# BlueBox-Amp_PA.net
KiCad netlist of a schematic drawn in Altium Designer
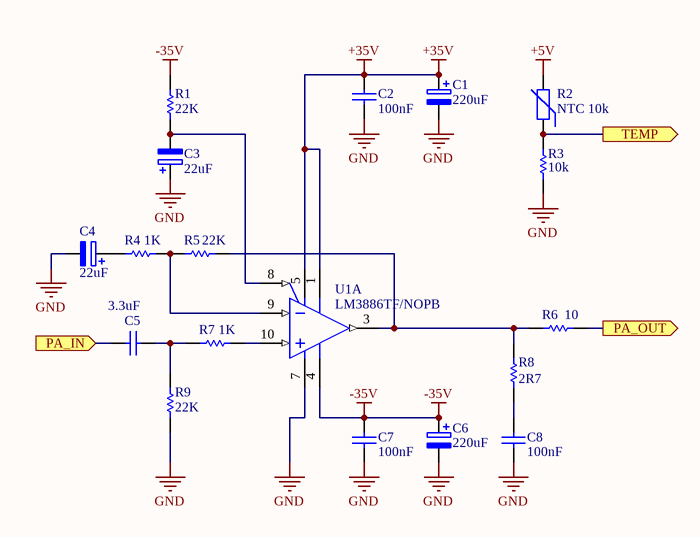
[diagram p0: BlueBox-Amp [PA].SchDoc]

(export (version "E")
  (design (tool "Eeschema 10.0.6"))
  (components
    (comp (ref "C1")
      (value "220uF")
      (footprint "E5-10,5")
      (description "Polarized Capacitor")
      (fields (field (name "Comment") "Capacitor Polarized"))
      (libsource (lib "") (part "Capacitor Polarized_1"))
    )
    (comp (ref "C2")
      (value "100nF")
      (footprint "CAPC0603(1608)100_L")
      (description "CAP 100nF 50V ±5% 0603 (1608 Metric) Thickness 1mm SMD")
      (fields (field (name "TOLERANCE") "±5%") (field (name "Comment") "CAP 100nF 50V 0603(1608)"))
      (libsource (lib "Altium Content Vault") (part "CMP-1035-02591-1"))
    )
    (comp (ref "C3")
      (value "22uF")
      (footprint "EC P2-D5-H11")
      (description "Polarized Capacitor")
      (fields (field (name "Comment") "Capacitor Polarized"))
      (libsource (lib "DEV - RLC") (part "Capacitor Polarized"))
    )
    (comp (ref "C4")
      (value "22uF")
      (footprint "EC P2-D5-H11")
      (description "Polarized Capacitor")
      (fields (field (name "Comment") "Capacitor Polarized"))
      (libsource (lib "") (part "Capacitor Polarized_2"))
    )
    (comp (ref "C5")
      (value "3.3uF")
      (footprint "CAPC1210(3225)280_L")
      (description "CAP 3.3uF 50V ±10% 1210 (3225 Metric) Thickness 2.8mm SMD")
      (fields (field (name "TOLERANCE") "±10%") (field (name "Comment") "CAP 3.3uF 50V 1210(3225)"))
      (libsource (lib "Altium Content Vault") (part "CMP-1038-02126-1"))
    )
    (comp (ref "C6")
      (value "220uF")
      (footprint "E5-10,5")
      (description "Polarized Capacitor")
      (fields (field (name "Comment") "Capacitor Polarized"))
      (libsource (lib "") (part "Capacitor Polarized_1"))
    )
    (comp (ref "C7")
      (value "100nF")
      (footprint "CAPC0603(1608)100_L")
      (description "CAP 100nF 50V ±5% 0603 (1608 Metric) Thickness 1mm SMD")
      (fields (field (name "TOLERANCE") "±5%") (field (name "Comment") "CAP 100nF 50V 0603(1608)"))
      (libsource (lib "Altium Content Vault") (part "CMP-1035-02591-1"))
    )
    (comp (ref "C8")
      (value "100nF")
      (footprint "CAPC0603(1608)100_L")
      (description "CAP 100nF 50V ±5% 0603 (1608 Metric) Thickness 1mm SMD")
      (fields (field (name "TOLERANCE") "±5%") (field (name "Comment") "CAP 100nF 50V 0603(1608)"))
      (libsource (lib "Altium Content Vault") (part "CMP-1035-02591-1"))
    )
    (comp (ref "R1")
      (value "22K")
      (footprint "RESC0603(1608)_L")
      (description "22K 0.1W 1% 0603 (1608 Metric)  SMD")
      (fields (field (name "POWER") "0.1 W") (field (name "TOLERANCE") "1 %"))
      (libsource (lib "Altium Content Vault") (part "CMP-1012-00659-1"))
    )
    (comp (ref "R2")
      (value "NTC 10k")
      (footprint "HDR1X2")
      (description "Thermistors - NTC 10k")
      (fields
        (field (name "MANUFACTURER") "Vishay / BC Components")
        (field (name "MANUFACTURER PART NUMBER") "NTCALUG02A103F")
      )
      (libsource (lib "DEV - Sensor") (part "NTCALUG02A103F"))
    )
    (comp (ref "R3")
      (value "10k")
      (footprint "RESC0603(1608)_M")
      (description "10K 0.1W 1% 0603 (1608 Metric)  SMD")
      (fields (field (name "POWER") "0.1 W") (field (name "TOLERANCE") "1 %"))
      (libsource (lib "Altium Content Vault") (part "CMP-1012-00623-1"))
    )
    (comp (ref "R4")
      (value "1K")
      (footprint "RESC0603(1608)_M")
      (description "1K 0.1W 1% 0603 (1608 Metric)  SMD")
      (fields (field (name "TOLERANCE") "1 %") (field (name "POWER") "0.1 W"))
      (libsource (lib "Altium Content Vault") (part "CMP-1012-00510-1"))
    )
    (comp (ref "R5")
      (value "22K")
      (footprint "RESC0603(1608)_L")
      (description "22K 0.1W 1% 0603 (1608 Metric)  SMD")
      (fields (field (name "POWER") "0.1 W") (field (name "TOLERANCE") "1 %"))
      (libsource (lib "Altium Content Vault") (part "CMP-1012-00659-1"))
    )
    (comp (ref "R6")
      (value "10")
      (footprint "RESC2512(6432)_L")
      (description "10R 1W 5% 2512 (6432 Metric)  SMD")
      (fields (field (name "POWER") "1 W") (field (name "TOLERANCE") "5 %"))
      (libsource (lib "Altium Content Vault") (part "CMP-1018-00026-1"))
    )
    (comp (ref "R7")
      (value "1K")
      (footprint "RESC0603(1608)_M")
      (description "1K 0.1W 1% 0603 (1608 Metric)  SMD")
      (fields (field (name "TOLERANCE") "1 %") (field (name "POWER") "0.1 W"))
      (libsource (lib "Altium Content Vault") (part "CMP-1012-00510-1"))
    )
    (comp (ref "R8")
      (value "2R7")
      (footprint "RESC2512(6432)_L")
      (description "2R7 1W 5% 2512 (6432 Metric)  SMD")
      (fields (field (name "TOLERANCE") "5 %") (field (name "POWER") "1 W"))
      (libsource (lib "Altium Content Vault") (part "CMP-1018-00012-1"))
    )
    (comp (ref "R9")
      (value "22K")
      (footprint "RESC0603(1608)_L")
      (description "22K 0.1W 1% 0603 (1608 Metric)  SMD")
      (fields (field (name "POWER") "0.1 W") (field (name "TOLERANCE") "1 %"))
      (libsource (lib "Altium Content Vault") (part "CMP-1012-00659-1"))
    )
    (comp (ref "U1")
      (value "LM3886TF/NOPB")
      (footprint "TI-NDA11")
      (fields (field (name "MANUFACTURER") "Texas Instruments"))
      (libsource (lib "Altium Content Vault") (part "TI-LM3886undefined"))
    )
  )
  (nets
    (net (code "1") (name "+5V") (class "Default")
      (node (ref "R2") (pin "2") (pinfunction "2_2") (pintype "passive"))
    )
    (net (code "2") (name "+35V") (class "Default")
      (node (ref "C1") (pin "1") (pinfunction "1_1") (pintype "passive"))
      (node (ref "C2") (pin "2") (pinfunction "2_2") (pintype "passive"))
      (node (ref "U1") (pin "1") (pinfunction "V+_1") (pintype "power_in"))
      (node (ref "U1") (pin "5") (pinfunction "V+_5") (pintype "power_in"))
    )
    (net (code "3") (name "-35V") (class "Default")
      (node (ref "C6") (pin "1") (pinfunction "1_1") (pintype "passive"))
      (node (ref "C7") (pin "2") (pinfunction "2_2") (pintype "passive"))
      (node (ref "R1") (pin "1") (pinfunction "1_1") (pintype "passive"))
      (node (ref "U1") (pin "4") (pinfunction "V-_4") (pintype "power_in"))
    )
    (net (code "4") (name "/PA_IN") (class "Default")
      (node (ref "C5") (pin "1") (pinfunction "1_1") (pintype "passive"))
    )
    (net (code "5") (name "/PA_OUT") (class "Default")
      (node (ref "R6") (pin "2") (pinfunction "2_2") (pintype "passive"))
    )
    (net (code "6") (name "/TEMP") (class "Default")
      (node (ref "R2") (pin "1") (pinfunction "1_1") (pintype "passive"))
      (node (ref "R3") (pin "2") (pinfunction "2_2") (pintype "passive"))
    )
    (net (code "7") (name "GND") (class "Default")
      (node (ref "C1") (pin "2") (pinfunction "2_2") (pintype "passive"))
      (node (ref "C2") (pin "1") (pinfunction "1_1") (pintype "passive"))
      (node (ref "C3") (pin "1") (pinfunction "1_1") (pintype "passive"))
      (node (ref "C4") (pin "2") (pinfunction "2_2") (pintype "passive"))
      (node (ref "C6") (pin "2") (pinfunction "2_2") (pintype "passive"))
      (node (ref "C7") (pin "1") (pinfunction "1_1") (pintype "passive"))
      (node (ref "C8") (pin "2") (pinfunction "2_2") (pintype "passive"))
      (node (ref "R3") (pin "1") (pinfunction "1_1") (pintype "passive"))
      (node (ref "R9") (pin "2") (pinfunction "2_2") (pintype "passive"))
      (node (ref "U1") (pin "7") (pinfunction "GND_7") (pintype "power_in"))
    )
    (net (code "8") (name "Net-(C4-Pad1)") (class "Default")
      (node (ref "C4") (pin "1") (pinfunction "1_1") (pintype "passive"))
      (node (ref "R4") (pin "1") (pinfunction "1_1") (pintype "passive"))
    )
    (net (code "9") (name "Net-(C5-Pad2)") (class "Default")
      (node (ref "C5") (pin "2") (pinfunction "2_2") (pintype "passive"))
      (node (ref "R7") (pin "1") (pinfunction "1_1") (pintype "passive"))
      (node (ref "R9") (pin "1") (pinfunction "1_1") (pintype "passive"))
    )
    (net (code "10") (name "Net-(C8-Pad1)") (class "Default")
      (node (ref "C8") (pin "1") (pinfunction "1_1") (pintype "passive"))
      (node (ref "R8") (pin "1") (pinfunction "1_1") (pintype "passive"))
    )
    (net (code "11") (name "Net-(U1A-MUTE)") (class "Default")
      (node (ref "C3") (pin "2") (pinfunction "2_2") (pintype "passive"))
      (node (ref "R1") (pin "2") (pinfunction "2_2") (pintype "passive"))
      (node (ref "U1") (pin "8") (pinfunction "MUTE_8") (pintype "input"))
    )
    (net (code "12") (name "Net-(U1A-OUTPUT)") (class "Default")
      (node (ref "R5") (pin "2") (pinfunction "2_2") (pintype "passive"))
      (node (ref "R6") (pin "1") (pinfunction "1_1") (pintype "passive"))
      (node (ref "R8") (pin "2") (pinfunction "2_2") (pintype "passive"))
      (node (ref "U1") (pin "3") (pinfunction "OUTPUT_3") (pintype "output"))
    )
    (net (code "13") (name "Net-(U1A-VIN+)") (class "Default")
      (node (ref "R7") (pin "2") (pinfunction "2_2") (pintype "passive"))
      (node (ref "U1") (pin "10") (pinfunction "VIN+_10") (pintype "input"))
    )
    (net (code "14") (name "Net-(U1A-VIN-)") (class "Default")
      (node (ref "R4") (pin "2") (pinfunction "2_2") (pintype "passive"))
      (node (ref "R5") (pin "1") (pinfunction "1_1") (pintype "passive"))
      (node (ref "U1") (pin "9") (pinfunction "VIN-_9") (pintype "input"))
    )
  )
)
